# AudioBoard.net
KiCad netlist of a schematic drawn in Altium Designer
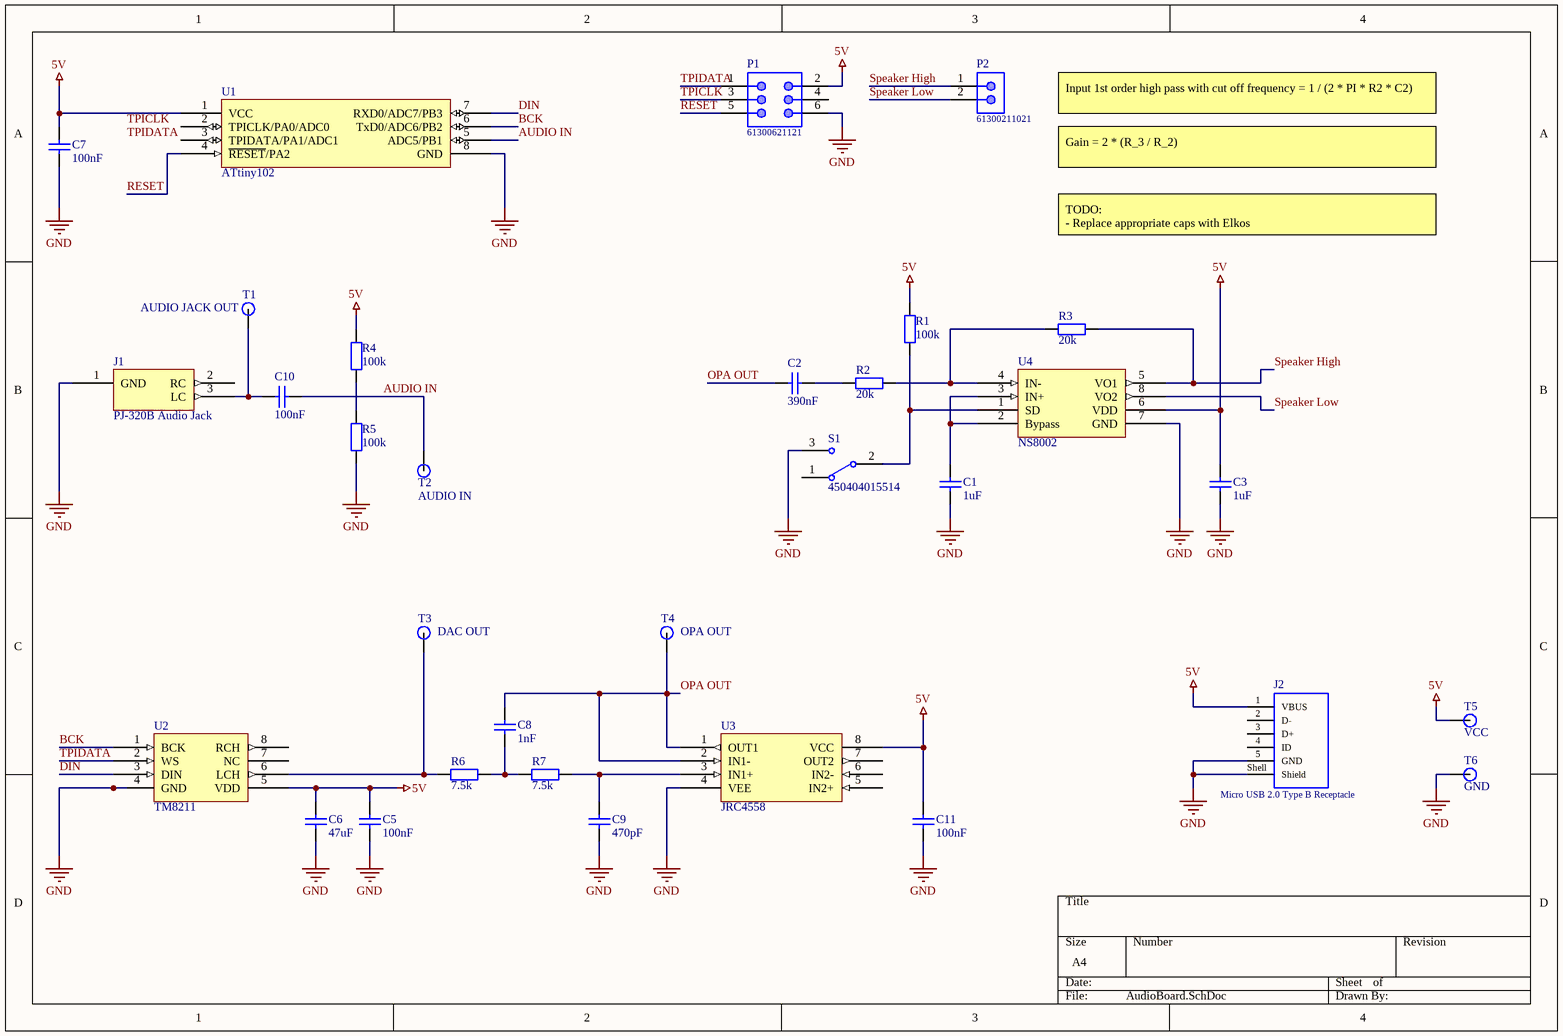
[diagram p0: AudioBoard.SchDoc]

(export (version "E")
  (design (tool "Eeschema 10.0.6"))
  (components
    (comp (ref "C1")
      (value "1uF")
      (footprint "WCAP-CSGP_0805_H=1.25mm")
      (description "WCAP-CSGP General Purpose Ceramic Capacitors, size 0805, 1uF, +/-10%, 10VDC")
      (fields (field (name "PART NUMBER") "885012207022") (field (name "PUBLISHER") "Wurth Elektronik"))
      (libsource (lib "Altium_WCAP-CSGP (rev19a)") (part "885012207022"))
    )
    (comp (ref "C2")
      (value "390nF")
      (footprint "WCAP-CSGP_0402")
      (description "WCAP-CSGP General Purpose Ceramic Capacitors, size 0402, 1nF, +/-10%, 16VDC")
      (fields (field (name "PART NUMBER") "885012205025") (field (name "PUBLISHER") "Wurth Elektronik"))
      (libsource (lib "Altium_WCAP-CSGP (rev19a)") (part "885012205025"))
    )
    (comp (ref "C3")
      (value "1uF")
      (footprint "WCAP-CSGP_0805_H=1.25mm")
      (description "WCAP-CSGP General Purpose Ceramic Capacitors, size 0805, 1uF, +/-10%, 10VDC")
      (fields (field (name "PART NUMBER") "885012207022") (field (name "PUBLISHER") "Wurth Elektronik"))
      (libsource (lib "Altium_WCAP-CSGP (rev19a)") (part "885012207022"))
    )
    (comp (ref "C5")
      (value "100nF")
      (footprint "WCAP-CSGP_0805_H=1.25mm")
      (description "WCAP-CSGP General Purpose Ceramic Capacitors, size 0805, 1uF, +/-10%, 10VDC")
      (fields (field (name "PART NUMBER") "885012207022") (field (name "PUBLISHER") "Wurth Elektronik"))
      (libsource (lib "Altium_WCAP-CSGP (rev19a)") (part "885012207022"))
    )
    (comp (ref "C6")
      (value "47uF")
      (footprint "WCAP-CSGP_0805_H=1.25mm")
      (description "WCAP-CSGP General Purpose Ceramic Capacitors, size 0805, 1uF, +/-10%, 10VDC")
      (fields (field (name "PART NUMBER") "885012207022") (field (name "PUBLISHER") "Wurth Elektronik"))
      (libsource (lib "Altium_WCAP-CSGP (rev19a)") (part "885012207022"))
    )
    (comp (ref "C7")
      (value "100nF")
      (footprint "WCAP-CSGP_0805_H=1.25mm")
      (description "WCAP-CSGP General Purpose Ceramic Capacitors, size 0805, 1uF, +/-10%, 10VDC")
      (fields (field (name "PART NUMBER") "885012207022") (field (name "PUBLISHER") "Wurth Elektronik"))
      (libsource (lib "Altium_WCAP-CSGP (rev19a)") (part "885012207022"))
    )
    (comp (ref "C8")
      (value "1nF")
      (footprint "WCAP-CSGP_0402")
      (description "WCAP-CSGP General Purpose Ceramic Capacitors, size 0402, 1nF, +/-10%, 16VDC")
      (fields (field (name "PART NUMBER") "885012205025") (field (name "PUBLISHER") "Wurth Elektronik"))
      (libsource (lib "Altium_WCAP-CSGP (rev19a)") (part "885012205025"))
    )
    (comp (ref "C9")
      (value "470pF")
      (footprint "WCAP-CSGP_0402")
      (description "WCAP-CSGP General Purpose Ceramic Capacitors, size 0402, 1nF, +/-10%, 16VDC")
      (fields (field (name "PART NUMBER") "885012205025") (field (name "PUBLISHER") "Wurth Elektronik"))
      (libsource (lib "Altium_WCAP-CSGP (rev19a)") (part "885012205025"))
    )
    (comp (ref "C10")
      (value "100nF")
      (footprint "WCAP-CSGP_0805_H=1.25mm")
      (description "WCAP-CSGP General Purpose Ceramic Capacitors, size 0805, 1uF, +/-10%, 10VDC")
      (fields (field (name "PART NUMBER") "885012207022") (field (name "PUBLISHER") "Wurth Elektronik"))
      (libsource (lib "Altium_WCAP-CSGP (rev19a)") (part "885012207022"))
    )
    (comp (ref "C11")
      (value "100nF")
      (footprint "WCAP-CSGP_0805_H=1.25mm")
      (description "WCAP-CSGP General Purpose Ceramic Capacitors, size 0805, 1uF, +/-10%, 10VDC")
      (fields (field (name "PART NUMBER") "885012207022") (field (name "PUBLISHER") "Wurth Elektronik"))
      (libsource (lib "Altium_WCAP-CSGP (rev19a)") (part "885012207022"))
    )
    (comp (ref "J1")
      (value "PJ-320B Audio Jack")
      (footprint "PJ-320B Audio Jack")
      (libsource (lib "PJ-320B_AudioJack") (part "PJ-320B Audio Jack"))
    )
    (comp (ref "J2")
      (value "Micro USB 2.0 Type B Receptacle")
      (footprint "629105136821")
      (description "Micro USB 2.0 Type B, Receptacle, Horizontal, SMT")
      (fields
        (field (name "MANUFACTURER") "Wurth Elektronik")
        (field (name "MANUFACTURER PART NUMBER") "629105136821")
      )
      (libsource (lib "Altium_WR-USB (rev21a)") (part "629105136821"))
    )
    (comp (ref "P1")
      (value "61300621121")
      (footprint "61300621121")
      (description "WR-PHD Pin Header, THT, pitch 2.54mm, Dual Row, Vertical, 6p")
      (fields (field (name "MANUFACTURER") "Wurth Elektronik"))
      (libsource (lib "61300311021_Altium_WR-PHD_rev20a") (part "61300621121"))
    )
    (comp (ref "P2")
      (value "61300211021")
      (footprint "61300211021")
      (description "WR-PHD Pin Header, THT, pitch 2.54mm, Single Row, Angled, 2p")
      (fields (field (name "MANUFACTURER") "Wurth Elektronik"))
      (libsource (lib "61300311021_Altium_WR-PHD_rev20a") (part "61300211021"))
    )
    (comp (ref "R1")
      (value "100k")
      (footprint "WRIS-PSMB_0805_H=0.22mm")
      (description "WRIS-PSMB Metal Plate Resistors, size 0805, 10mOhm, +/-1%, 0.5W")
      (fields (field (name "PART NUMBER") "580060720008") (field (name "PUBLISHER") "Wurth Elektronik"))
      (libsource (lib "") (part "580060720008_2"))
    )
    (comp (ref "R2")
      (value "20k")
      (footprint "0402 Resistor")
      (description "CRG0402 1% 2K0")
      (fields (field (name "MF") "{'manufacturer': u'TE Connectivity'}") (field (name "MP") "4-1676480-2"))
      (libsource (lib "0402 Resistor") (part "Resistor"))
    )
    (comp (ref "R3")
      (value "20k")
      (footprint "0402 Resistor")
      (description "CRG0402 1% 2K0")
      (fields (field (name "MF") "{'manufacturer': u'TE Connectivity'}") (field (name "MP") "4-1676480-2"))
      (libsource (lib "0402 Resistor") (part "Resistor"))
    )
    (comp (ref "R4")
      (value "100k")
      (footprint "WRIS-PSMB_0805_H=0.22mm")
      (description "WRIS-PSMB Metal Plate Resistors, size 0805, 10mOhm, +/-1%, 0.5W")
      (fields (field (name "PART NUMBER") "580060720008") (field (name "PUBLISHER") "Wurth Elektronik"))
      (libsource (lib "") (part "580060720008_1"))
    )
    (comp (ref "R5")
      (value "100k")
      (footprint "WRIS-PSMB_0805_H=0.22mm")
      (description "WRIS-PSMB Metal Plate Resistors, size 0805, 10mOhm, +/-1%, 0.5W")
      (fields (field (name "PART NUMBER") "580060720008") (field (name "PUBLISHER") "Wurth Elektronik"))
      (libsource (lib "") (part "580060720008_1"))
    )
    (comp (ref "R6")
      (value "7.5k")
      (footprint "WRIS-PSMB_0805_H=0.22mm")
      (description "WRIS-PSMB Metal Plate Resistors, size 0805, 10mOhm, +/-1%, 0.5W")
      (fields (field (name "PART NUMBER") "580060720008") (field (name "PUBLISHER") "Wurth Elektronik"))
      (libsource (lib "Altium_WRIS-PSMB (rev19a)") (part "580060720008"))
    )
    (comp (ref "R7")
      (value "7.5k")
      (footprint "WRIS-PSMB_0805_H=0.22mm")
      (description "WRIS-PSMB Metal Plate Resistors, size 0805, 10mOhm, +/-1%, 0.5W")
      (fields (field (name "PART NUMBER") "580060720008") (field (name "PUBLISHER") "Wurth Elektronik"))
      (libsource (lib "Altium_WRIS-PSMB (rev19a)") (part "580060720008"))
    )
    (comp (ref "S1")
      (value "450404015514")
      (footprint "450404015514")
      (description "WS-SLSU Mini SMT Slide Switch, Same Side Connection, Right Angled, SPDT")
      (fields (field (name "PUBLISHER") "Wurth Elektronik"))
      (libsource (lib "Altium_WS-SLSU (rev19b)") (part "450404015514"))
    )
    (comp (ref "T1")
      (value "AUDIO JACK OUT")
      (footprint "Testpoint")
      (libsource (lib "Testpoint") (part "Testpoint"))
    )
    (comp (ref "T2")
      (value "AUDIO IN")
      (footprint "Testpoint")
      (libsource (lib "Testpoint") (part "Testpoint"))
    )
    (comp (ref "T3")
      (value "DAC OUT")
      (footprint "Testpoint")
      (libsource (lib "Testpoint") (part "Testpoint"))
    )
    (comp (ref "T4")
      (value "OPA OUT")
      (footprint "Testpoint")
      (libsource (lib "Testpoint") (part "Testpoint"))
    )
    (comp (ref "T5") (value "VCC") (footprint "Testpoint") (libsource (lib "Testpoint") (part "Testpoint")))
    (comp (ref "T6") (value "GND") (footprint "Testpoint") (libsource (lib "Testpoint") (part "Testpoint")))
    (comp (ref "U1")
      (value "ATtiny102")
      (footprint "ATtiny102")
      (libsource (lib "ATtiny102") (part "ATtiny102"))
    )
    (comp (ref "U2") (value "TM8211") (footprint "TM8211") (libsource (lib "TM8211") (part "TM8211")))
    (comp (ref "U3") (value "JRC4558") (footprint "JRC4558") (libsource (lib "JRC4558") (part "JRC4558")))
    (comp (ref "U4") (value "NS8002") (footprint "NS8002") (libsource (lib "NS8002") (part "NS8002")))
  )
  (nets
    (net (code "1") (name "/AUDIO IN") (class "Default")
      (node (ref "C10") (pin "2") (pinfunction "2_2") (pintype "passive"))
      (node (ref "T2") (pin "1") (pinfunction "1_1") (pintype "passive"))
      (node (ref "U1") (pin "5") (pinfunction "ADC5/PB1_5") (pintype "bidirectional"))
    )
    (net (code "2") (name "/BCK") (class "Default")
      (node (ref "U1") (pin "6") (pinfunction "TxD0/ADC6/PB2_6") (pintype "bidirectional"))
      (node (ref "U2") (pin "1") (pinfunction "BCK_1") (pintype "input"))
    )
    (net (code "3") (name "/DIN") (class "Default")
      (node (ref "U1") (pin "7") (pinfunction "RXD0/ADC7/PB3_7") (pintype "bidirectional"))
      (node (ref "U2") (pin "3") (pinfunction "DIN_3") (pintype "input"))
    )
    (net (code "4") (name "/OPA OUT") (class "Default")
      (node (ref "C2") (pin "2") (pinfunction "2_2") (pintype "passive"))
      (node (ref "C8") (pin "2") (pinfunction "2_2") (pintype "passive"))
      (node (ref "T4") (pin "1") (pinfunction "1_1") (pintype "passive"))
      (node (ref "U3") (pin "1") (pinfunction "OUT1_1") (pintype "output"))
      (node (ref "U3") (pin "2") (pinfunction "IN1-_2") (pintype "input"))
    )
    (net (code "5") (name "/RESET") (class "Default")
      (node (ref "P1") (pin "5") (pinfunction "5_5") (pintype "passive"))
      (node (ref "U1") (pin "4") (pinfunction "~{RESET}/PA2_4") (pintype "input"))
    )
    (net (code "6") (name "/Speaker High") (class "Default")
      (node (ref "P2") (pin "1") (pinfunction "1_1") (pintype "passive"))
      (node (ref "R3") (pin "2") (pinfunction "2_2") (pintype "passive"))
      (node (ref "U4") (pin "5") (pinfunction "VO1_5") (pintype "output"))
    )
    (net (code "7") (name "/Speaker Low") (class "Default")
      (node (ref "P2") (pin "2") (pinfunction "2_2") (pintype "passive"))
      (node (ref "U4") (pin "8") (pinfunction "VO2_8") (pintype "output"))
    )
    (net (code "8") (name "/TPICLK") (class "Default")
      (node (ref "P1") (pin "3") (pinfunction "3_3") (pintype "passive"))
    )
    (net (code "9") (name "/TPIDATA") (class "Default")
      (node (ref "P1") (pin "1") (pinfunction "1_1") (pintype "passive"))
      (node (ref "U2") (pin "2") (pinfunction "WS_2") (pintype "input"))
    )
    (net (code "10") (name "5V") (class "Default")
      (node (ref "C11") (pin "1") (pinfunction "1_1") (pintype "passive"))
      (node (ref "C3") (pin "1") (pinfunction "1_1") (pintype "passive"))
      (node (ref "C5") (pin "1") (pinfunction "1_1") (pintype "passive"))
      (node (ref "C6") (pin "1") (pinfunction "1_1") (pintype "passive"))
      (node (ref "C7") (pin "1") (pinfunction "1_1") (pintype "passive"))
      (node (ref "J2") (pin "1") (pinfunction "VBUS_1") (pintype "passive"))
      (node (ref "P1") (pin "2") (pinfunction "2_2") (pintype "passive"))
      (node (ref "R1") (pin "2") (pinfunction "2_2") (pintype "passive"))
      (node (ref "R4") (pin "1") (pinfunction "1_1") (pintype "passive"))
      (node (ref "T5") (pin "1") (pinfunction "1_1") (pintype "passive"))
      (node (ref "U1") (pin "1") (pinfunction "VCC_1") (pintype "power_in"))
      (node (ref "U2") (pin "5") (pinfunction "VDD_5") (pintype "power_in"))
      (node (ref "U3") (pin "8") (pinfunction "VCC_8") (pintype "power_in"))
      (node (ref "U4") (pin "6") (pinfunction "VDD_6") (pintype "power_in"))
    )
    (net (code "11") (name "GND") (class "Default")
      (node (ref "C1") (pin "1") (pinfunction "1_1") (pintype "passive"))
      (node (ref "C11") (pin "2") (pinfunction "2_2") (pintype "passive"))
      (node (ref "C3") (pin "2") (pinfunction "2_2") (pintype "passive"))
      (node (ref "C5") (pin "2") (pinfunction "2_2") (pintype "passive"))
      (node (ref "C6") (pin "2") (pinfunction "2_2") (pintype "passive"))
      (node (ref "C7") (pin "2") (pinfunction "2_2") (pintype "passive"))
      (node (ref "C9") (pin "1") (pinfunction "1_1") (pintype "passive"))
      (node (ref "J1") (pin "1") (pinfunction "GND_1") (pintype "passive"))
      (node (ref "J2") (pin "5") (pinfunction "GND_5") (pintype "passive"))
      (node (ref "J2") (pin "Shell") (pinfunction "Shield_Shell") (pintype "passive"))
      (node (ref "P1") (pin "6") (pinfunction "6_6") (pintype "passive"))
      (node (ref "R5") (pin "2") (pinfunction "2_2") (pintype "passive"))
      (node (ref "S1") (pin "3") (pinfunction "3_3") (pintype "passive"))
      (node (ref "T6") (pin "1") (pinfunction "1_1") (pintype "passive"))
      (node (ref "U1") (pin "8") (pinfunction "GND_8") (pintype "passive"))
      (node (ref "U2") (pin "4") (pinfunction "GND_4") (pintype "passive"))
      (node (ref "U3") (pin "4") (pinfunction "VEE_4") (pintype "passive"))
      (node (ref "U4") (pin "7") (pinfunction "GND_7") (pintype "passive"))
    )
    (net (code "12") (name "Net-(C2-Pad1)") (class "Default")
      (node (ref "C2") (pin "1") (pinfunction "1_1") (pintype "passive"))
      (node (ref "R2") (pin "1") (pinfunction "1_1") (pintype "passive"))
    )
    (net (code "13") (name "Net-(C8-Pad1)") (class "Default")
      (node (ref "C8") (pin "1") (pinfunction "1_1") (pintype "passive"))
      (node (ref "R6") (pin "2") (pinfunction "2_2") (pintype "passive"))
      (node (ref "R7") (pin "1") (pinfunction "1_1") (pintype "passive"))
    )
    (net (code "14") (name "Net-(J1-LC)") (class "Default")
      (node (ref "C10") (pin "1") (pinfunction "1_1") (pintype "passive"))
      (node (ref "J1") (pin "3") (pinfunction "LC_3") (pintype "output"))
      (node (ref "T1") (pin "1") (pinfunction "1_1") (pintype "passive"))
    )
    (net (code "15") (name "Net-(R4-Pad2)") (class "Default")
      (node (ref "R4") (pin "2") (pinfunction "2_2") (pintype "passive"))
      (node (ref "R5") (pin "1") (pinfunction "1_1") (pintype "passive"))
    )
    (net (code "16") (name "Net-(S1-COM)") (class "Default")
      (node (ref "R1") (pin "1") (pinfunction "1_1") (pintype "passive"))
      (node (ref "S1") (pin "2") (pinfunction "COM_2") (pintype "passive"))
      (node (ref "U4") (pin "1") (pinfunction "SD_1") (pintype "passive"))
    )
    (net (code "17") (name "Net-(U2-LCH)") (class "Default")
      (node (ref "R6") (pin "1") (pinfunction "1_1") (pintype "passive"))
      (node (ref "T3") (pin "1") (pinfunction "1_1") (pintype "passive"))
      (node (ref "U2") (pin "6") (pinfunction "LCH_6") (pintype "output"))
    )
    (net (code "18") (name "Net-(U3-IN1+)") (class "Default")
      (node (ref "C9") (pin "2") (pinfunction "2_2") (pintype "passive"))
      (node (ref "R7") (pin "2") (pinfunction "2_2") (pintype "passive"))
      (node (ref "U3") (pin "3") (pinfunction "IN1+_3") (pintype "input"))
    )
    (net (code "19") (name "Net-(U4-Bypass)") (class "Default")
      (node (ref "C1") (pin "2") (pinfunction "2_2") (pintype "passive"))
      (node (ref "U4") (pin "2") (pinfunction "Bypass_2") (pintype "passive"))
      (node (ref "U4") (pin "3") (pinfunction "IN+_3") (pintype "input"))
    )
    (net (code "20") (name "Net-(U4-IN-)") (class "Default")
      (node (ref "R2") (pin "2") (pinfunction "2_2") (pintype "passive"))
      (node (ref "R3") (pin "1") (pinfunction "1_1") (pintype "passive"))
      (node (ref "U4") (pin "4") (pinfunction "IN-_4") (pintype "input"))
    )
    (net (code "21") (name "unconnected-(J1-RC-Pad2)") (class "Default")
      (node (ref "J1") (pin "2") (pinfunction "RC_2") (pintype "output"))
    )
    (net (code "22") (name "unconnected-(J2-D+-Pad3)") (class "Default")
      (node (ref "J2") (pin "3") (pinfunction "D+_3") (pintype "passive"))
    )
    (net (code "23") (name "unconnected-(J2-D--Pad2)") (class "Default")
      (node (ref "J2") (pin "2") (pinfunction "D-_2") (pintype "passive"))
    )
    (net (code "24") (name "unconnected-(J2-ID-Pad4)") (class "Default")
      (node (ref "J2") (pin "4") (pinfunction "ID_4") (pintype "passive"))
    )
    (net (code "25") (name "unconnected-(P1-Pad4)") (class "Default")
      (node (ref "P1") (pin "4") (pinfunction "4_4") (pintype "passive"))
    )
    (net (code "26") (name "unconnected-(S1-Pad1)") (class "Default")
      (node (ref "S1") (pin "1") (pinfunction "1_1") (pintype "passive"))
    )
    (net (code "27") (name "unconnected-(U1-TPICLK{slash}PA0{slash}ADC0-Pad2)") (class "Default")
      (node (ref "U1") (pin "2") (pinfunction "TPICLK/PA0/ADC0_2") (pintype "bidirectional"))
    )
    (net (code "28") (name "unconnected-(U1-TPIDATA{slash}PA1{slash}ADC1-Pad3)") (class "Default")
      (node (ref "U1") (pin "3") (pinfunction "TPIDATA/PA1/ADC1_3") (pintype "bidirectional"))
    )
    (net (code "29") (name "unconnected-(U2-NC-Pad7)") (class "Default")
      (node (ref "U2") (pin "7") (pinfunction "NC_7") (pintype "open_collector"))
    )
    (net (code "30") (name "unconnected-(U2-RCH-Pad8)") (class "Default")
      (node (ref "U2") (pin "8") (pinfunction "RCH_8") (pintype "output"))
    )
    (net (code "31") (name "unconnected-(U3-IN2+-Pad5)") (class "Default")
      (node (ref "U3") (pin "5") (pinfunction "IN2+_5") (pintype "input"))
    )
    (net (code "32") (name "unconnected-(U3-IN2--Pad6)") (class "Default")
      (node (ref "U3") (pin "6") (pinfunction "IN2-_6") (pintype "input"))
    )
    (net (code "33") (name "unconnected-(U3-OUT2-Pad7)") (class "Default")
      (node (ref "U3") (pin "7") (pinfunction "OUT2_7") (pintype "output"))
    )
  )
)
